# schematic.net
KiCad netlist of a schematic drawn in EAGLE
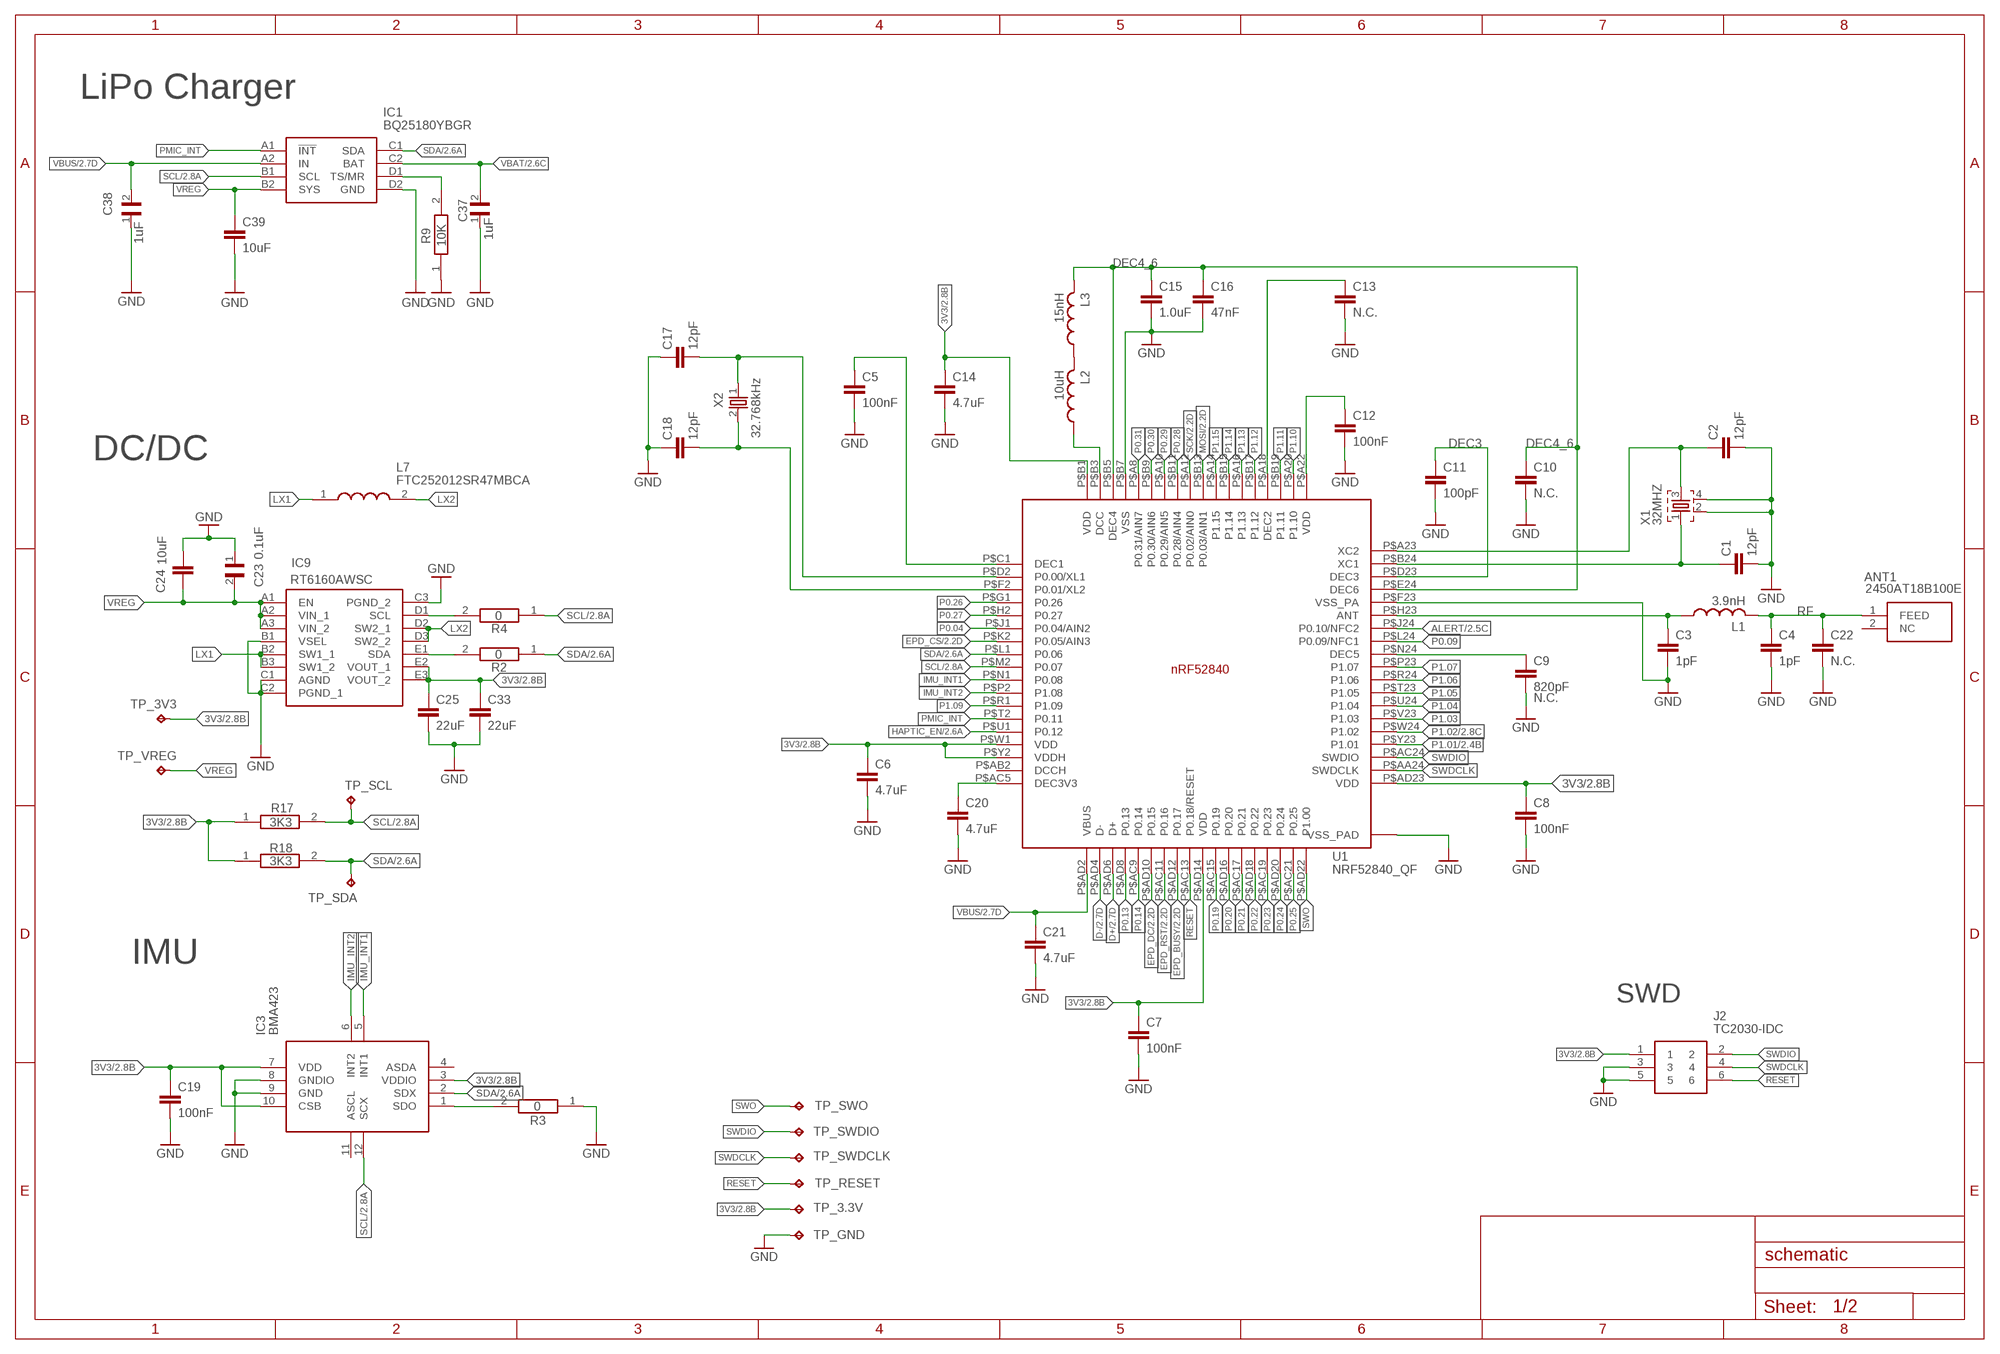
[diagram p0: schematic, sheet 1]
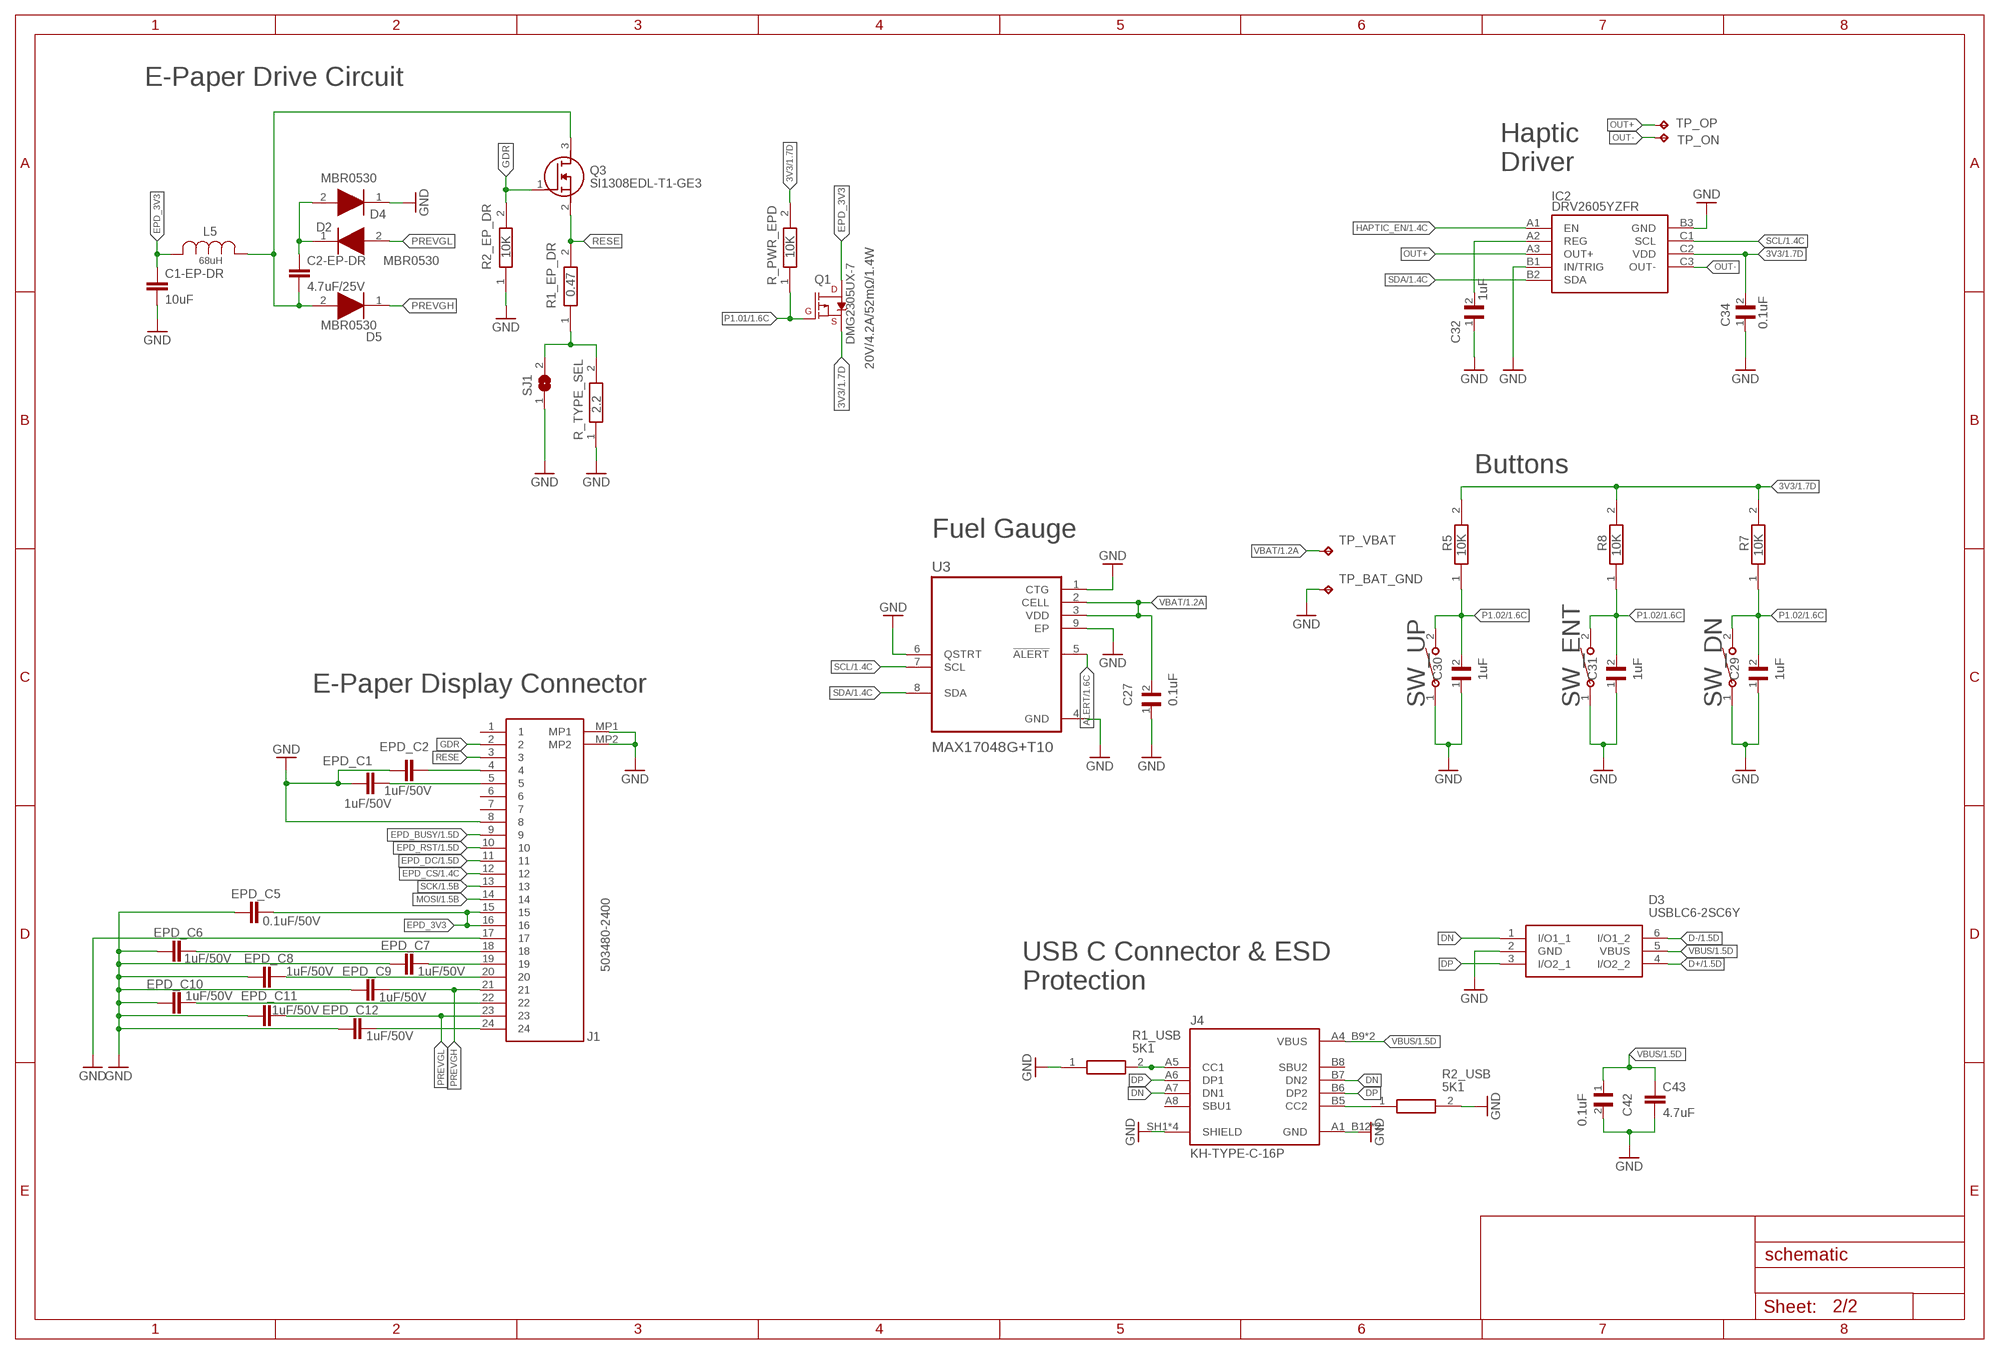
[diagram p1: schematic, sheet 2]

(export (version "E")
  (design (tool "Eeschema 10.0.6"))
  (components
    (comp (ref "ANT1")
      (value "2450AT18B100E")
      (footprint "eagle-import:2450AT18B100E_ANTC3216X140N")
      (fields (field (name "MOUSER_PART_NUMBER") "609-2450AT18B100E"))
      (libsource (lib "eagle-import") (part "2450AT18B100E_2450AT18B100E"))
    )
    (comp (ref "C1")
      (value "12pF")
      (footprint "eagle-import:NORDIC_NRF_3_RESC0201_L")
      (libsource (lib "eagle-import") (part "NORDIC_NRF_3_CAPACITOR_0201_L"))
    )
    (comp (ref "C2")
      (value "12pF")
      (footprint "eagle-import:NORDIC_NRF_3_RESC0201_L")
      (libsource (lib "eagle-import") (part "NORDIC_NRF_3_CAPACITOR_0201_L"))
    )
    (comp (ref "C3")
      (value "1pF")
      (footprint "eagle-import:NORDIC_NRF_3_RESC0201_L")
      (libsource (lib "eagle-import") (part "NORDIC_NRF_3_CAPACITOR_0201_L"))
    )
    (comp (ref "C4")
      (value "1pF")
      (footprint "eagle-import:NORDIC_NRF_3_RESC0201_L")
      (libsource (lib "eagle-import") (part "NORDIC_NRF_3_CAPACITOR_0201_L"))
    )
    (comp (ref "C5")
      (value "100nF")
      (footprint "eagle-import:NORDIC_NRF_3_RESC0201_L")
      (libsource (lib "eagle-import") (part "NORDIC_NRF_3_CAPACITOR_0201_L"))
    )
    (comp (ref "C6")
      (value "4.7uF")
      (footprint "eagle-import:NORDIC_NRF_3_RESC0402_L")
      (libsource (lib "eagle-import") (part "NORDIC_NRF_3_CAPACITOR_0402_L"))
    )
    (comp (ref "C7")
      (value "100nF")
      (footprint "eagle-import:NORDIC_NRF_3_RESC0201_L")
      (libsource (lib "eagle-import") (part "NORDIC_NRF_3_CAPACITOR_0201_L"))
    )
    (comp (ref "C8")
      (value "100nF")
      (footprint "eagle-import:NORDIC_NRF_3_RESC0201_L")
      (libsource (lib "eagle-import") (part "NORDIC_NRF_3_CAPACITOR_0201_L"))
    )
    (comp (ref "C9")
      (value "820pF")
      (footprint "eagle-import:NORDIC_NRF_3_RESC0201_L")
      (libsource (lib "eagle-import") (part "NORDIC_NRF_3_CAPACITOR_0201_L"))
    )
    (comp (ref "C10")
      (value "N.C.")
      (footprint "eagle-import:NORDIC_NRF_3_RESC0201_L")
      (libsource (lib "eagle-import") (part "NORDIC_NRF_3_CAPACITOR_0201_L"))
    )
    (comp (ref "C11")
      (value "100pF")
      (footprint "eagle-import:NORDIC_NRF_3_RESC0201_L")
      (libsource (lib "eagle-import") (part "NORDIC_NRF_3_CAPACITOR_0201_L"))
    )
    (comp (ref "C12")
      (value "100nF")
      (footprint "eagle-import:NORDIC_NRF_3_RESC0201_L")
      (libsource (lib "eagle-import") (part "NORDIC_NRF_3_CAPACITOR_0201_L"))
    )
    (comp (ref "C13")
      (value "N.C.")
      (footprint "eagle-import:NORDIC_NRF_3_RESC0201_L")
      (libsource (lib "eagle-import") (part "NORDIC_NRF_3_CAPACITOR_0201_L"))
    )
    (comp (ref "C14")
      (value "4.7uF")
      (footprint "eagle-import:NORDIC_NRF_3_RESC0201_L")
      (libsource (lib "eagle-import") (part "NORDIC_NRF_3_CAPACITOR_0201_L"))
    )
    (comp (ref "C15")
      (value "1.0uF")
      (footprint "eagle-import:NORDIC_NRF_3_RESC0201_L")
      (libsource (lib "eagle-import") (part "NORDIC_NRF_3_CAPACITOR_0201_L"))
    )
    (comp (ref "C16")
      (value "47nF")
      (footprint "eagle-import:NORDIC_NRF_3_RESC0201_L")
      (libsource (lib "eagle-import") (part "NORDIC_NRF_3_CAPACITOR_0201_L"))
    )
    (comp (ref "C17")
      (value "12pF")
      (footprint "eagle-import:PERFECT_0402_0402")
      (libsource (lib "eagle-import") (part "PERFECT_0402_CAP_0402"))
    )
    (comp (ref "C18")
      (value "12pF")
      (footprint "eagle-import:PERFECT_0402_0402")
      (libsource (lib "eagle-import") (part "PERFECT_0402_CAP_0402"))
    )
    (comp (ref "C19")
      (value "100nF")
      (footprint "eagle-import:PERFECT_0402_0402")
      (libsource (lib "eagle-import") (part "PERFECT_0402_CAP_0402"))
    )
    (comp (ref "C20")
      (value "4.7uF")
      (footprint "eagle-import:NORDIC_NRF_3_RESC0402_L")
      (libsource (lib "eagle-import") (part "NORDIC_NRF_3_CAPACITOR_0402_L"))
    )
    (comp (ref "C21")
      (value "4.7uF")
      (footprint "eagle-import:NORDIC_NRF_3_RESC0402_L")
      (libsource (lib "eagle-import") (part "NORDIC_NRF_3_CAPACITOR_0402_L"))
    )
    (comp (ref "C22")
      (value "N.C.")
      (footprint "eagle-import:NORDIC_NRF_3_RESC0201_L")
      (libsource (lib "eagle-import") (part "NORDIC_NRF_3_CAPACITOR_0201_L"))
    )
    (comp (ref "C23")
      (value "0.1uF")
      (footprint "eagle-import:GRM011R60J152KE01L_2_CAPC0201X13N")
      (fields (field (name "MF") "Murata") (field (name "MP") "GRM011R60J152KE01L"))
      (libsource (lib "eagle-import") (part "GRM011R60J152KE01L_2_GRM011R60J152KE01L"))
    )
    (comp (ref "C24")
      (value "10uF")
      (footprint "eagle-import:PERFECT_0402_0402")
      (libsource (lib "eagle-import") (part "PERFECT_0402_CAP_0402"))
    )
    (comp (ref "C25")
      (value "22uF")
      (footprint "eagle-import:PERFECT_0402_0402")
      (libsource (lib "eagle-import") (part "PERFECT_0402_CAP_0402"))
    )
    (comp (ref "C33")
      (value "22uF")
      (footprint "eagle-import:PERFECT_0402_0402")
      (libsource (lib "eagle-import") (part "PERFECT_0402_CAP_0402"))
    )
    (comp (ref "C37")
      (value "1uF")
      (footprint "eagle-import:GRM011R60J152KE01L_2_CAPC0201X13N")
      (fields (field (name "MF") "Murata") (field (name "MP") "GRM011R60J152KE01L"))
      (libsource (lib "eagle-import") (part "GRM011R60J152KE01L_2_GRM011R60J152KE01L"))
    )
    (comp (ref "C38")
      (value "1uF")
      (footprint "eagle-import:GRM011R60J152KE01L_2_CAPC0201X13N")
      (fields (field (name "MF") "Murata") (field (name "MP") "GRM011R60J152KE01L"))
      (libsource (lib "eagle-import") (part "GRM011R60J152KE01L_2_GRM011R60J152KE01L"))
    )
    (comp (ref "C39")
      (value "10uF")
      (footprint "eagle-import:PERFECT_0402_0402")
      (libsource (lib "eagle-import") (part "PERFECT_0402_CAP_0402"))
    )
    (comp (ref "IC1")
      (value "BQ25180YBGR")
      (footprint "eagle-import:BQ25180YBGR_BGA8C40P2X4_100X155X50")
      (fields (field (name "MOUSER_PART_NUMBER") "595-BQ25180YBGR"))
      (libsource (lib "eagle-import") (part "BQ25180YBGR_BQ25180YBGR"))
    )
    (comp (ref "IC3")
      (value "BMA423")
      (footprint "eagle-import:BMA423_BMA423")
      (fields (field (name "MOUSER_PART_NUMBER") "262-BMA423"))
      (libsource (lib "eagle-import") (part "BMA423_BMA423"))
    )
    (comp (ref "IC9")
      (value "RT6160AWSC")
      (footprint "eagle-import:RT6160AWSC_BGA15C40P3X5_140X230X60")
      (fields (field (name "MOUSER_PART_NUMBER") "835-RT6160AWSC"))
      (libsource (lib "eagle-import") (part "RT6160AWSC_RT6160AWSC"))
    )
    (comp (ref "J2")
      (value "TC2030-IDC")
      (footprint "eagle-import:TC2030-IDC_TC2030IDC")
      (libsource (lib "eagle-import") (part "TC2030-IDC_TC2030-IDC"))
    )
    (comp (ref "L1")
      (value "3.9nH")
      (footprint "eagle-import:NORDIC_NRF_2_RESC0201_L")
      (libsource (lib "eagle-import") (part "NORDIC_NRF_2_INDUCTOR_0201_L"))
    )
    (comp (ref "L2")
      (value "10uH")
      (footprint "eagle-import:NORDIC_NRF_2_RESC0402_L")
      (libsource (lib "eagle-import") (part "NORDIC_NRF_2_INDUCTOR_0402_L"))
    )
    (comp (ref "L3")
      (value "15nH")
      (footprint "eagle-import:NORDIC_NRF_2_RESC0402_L")
      (libsource (lib "eagle-import") (part "NORDIC_NRF_2_INDUCTOR_0402_L"))
    )
    (comp (ref "L7")
      (value "FTC252012SR47MBCA")
      (footprint "eagle-import:MLP2016SR47MT0S1_INDC2016X100N")
      (libsource (lib "eagle-import") (part "MLP2016SR47MT0S1_FTC252012SR47MBCA"))
    )
    (comp (ref "R2")
      (value "0")
      (footprint "eagle-import:ERA-1AEB3401C_0201")
      (libsource (lib "eagle-import") (part "ERA-1AEB3401C_CPF0201D7K68C1"))
    )
    (comp (ref "R3")
      (value "0")
      (footprint "eagle-import:CPF0201D7K68C1_0201")
      (libsource (lib "eagle-import") (part "CPF0201D7K68C1_CPF0201D7K68C1"))
    )
    (comp (ref "R4")
      (value "0")
      (footprint "eagle-import:ERA-1AEB3401C_0201")
      (libsource (lib "eagle-import") (part "ERA-1AEB3401C_CPF0201D7K68C1"))
    )
    (comp (ref "R9")
      (value "10K")
      (footprint "eagle-import:CPF0201D7K68C1_0201")
      (libsource (lib "eagle-import") (part "CPF0201D7K68C1_CPF0201D7K68C1"))
    )
    (comp (ref "R17")
      (value "3K3")
      (footprint "eagle-import:CPF0201D7K68C1_0201")
      (libsource (lib "eagle-import") (part "CPF0201D7K68C1_CPF0201D7K68C1"))
    )
    (comp (ref "R18")
      (value "3K3")
      (footprint "eagle-import:CPF0201D7K68C1_0201")
      (libsource (lib "eagle-import") (part "CPF0201D7K68C1_CPF0201D7K68C1"))
    )
    (comp (ref "TP_3.3V")
      (value "HECTOR_WATCH_1_TPTP20R")
      (footprint "eagle-import:HECTOR_WATCH_1_TP20R")
      (libsource (lib "eagle-import") (part "HECTOR_WATCH_1_TPTP20R"))
    )
    (comp (ref "TP_3V3")
      (value "HECTOR_WATCH_1_TPTP20R")
      (footprint "eagle-import:HECTOR_WATCH_1_TP20R")
      (libsource (lib "eagle-import") (part "HECTOR_WATCH_1_TPTP20R"))
    )
    (comp (ref "TP_GND")
      (value "HECTOR_WATCH_1_TPTP20R")
      (footprint "eagle-import:HECTOR_WATCH_1_TP20R")
      (libsource (lib "eagle-import") (part "HECTOR_WATCH_1_TPTP20R"))
    )
    (comp (ref "TP_RESET")
      (value "HECTOR_WATCH_1_TPTP20R")
      (footprint "eagle-import:HECTOR_WATCH_1_TP20R")
      (libsource (lib "eagle-import") (part "HECTOR_WATCH_1_TPTP20R"))
    )
    (comp (ref "TP_SCL")
      (value "HECTOR_WATCH_1_TPTP20R")
      (footprint "eagle-import:HECTOR_WATCH_1_TP20R")
      (libsource (lib "eagle-import") (part "HECTOR_WATCH_1_TPTP20R"))
    )
    (comp (ref "TP_SDA")
      (value "HECTOR_WATCH_1_TPTP20R")
      (footprint "eagle-import:HECTOR_WATCH_1_TP20R")
      (libsource (lib "eagle-import") (part "HECTOR_WATCH_1_TPTP20R"))
    )
    (comp (ref "TP_SWDCLK")
      (value "HECTOR_WATCH_1_TPTP20R")
      (footprint "eagle-import:HECTOR_WATCH_1_TP20R")
      (libsource (lib "eagle-import") (part "HECTOR_WATCH_1_TPTP20R"))
    )
    (comp (ref "TP_SWDIO")
      (value "HECTOR_WATCH_1_TPTP20R")
      (footprint "eagle-import:HECTOR_WATCH_1_TP20R")
      (libsource (lib "eagle-import") (part "HECTOR_WATCH_1_TPTP20R"))
    )
    (comp (ref "TP_SWO")
      (value "HECTOR_WATCH_1_TPTP20R")
      (footprint "eagle-import:HECTOR_WATCH_1_TP20R")
      (libsource (lib "eagle-import") (part "HECTOR_WATCH_1_TPTP20R"))
    )
    (comp (ref "TP_VREG")
      (value "HECTOR_WATCH_1_TPTP20R")
      (footprint "eagle-import:HECTOR_WATCH_1_TP20R")
      (libsource (lib "eagle-import") (part "HECTOR_WATCH_1_TPTP20R"))
    )
    (comp (ref "U1")
      (value "NRF52840_QF")
      (footprint "eagle-import:NORDIC_NRF_4_AQFN50P700X700X85_HS-74N")
      (libsource (lib "eagle-import") (part "NORDIC_NRF_4_NRF52840_QF"))
    )
    (comp (ref "X1")
      (value "32MHZ")
      (footprint "eagle-import:NORDIC_NRF_BT-XTAL_2016_N")
      (libsource (lib "eagle-import") (part "NORDIC_NRF_XTAL_32MHZ"))
    )
    (comp (ref "X2")
      (value "32.768kHz")
      (footprint "eagle-import:NORDIC_NRF_1_XTAL_3215_N")
      (libsource (lib "eagle-import") (part "NORDIC_NRF_1_XTAL_32KHZ"))
    )
    (comp (ref "C1-EP-DR")
      (value "10uF")
      (footprint "eagle-import:NORDIC_NRF_3_RESC0402_L")
      (libsource (lib "eagle-import") (part "NORDIC_NRF_3_CAPACITOR_0402_L"))
    )
    (comp (ref "C2-EP-DR")
      (value "4.7uF/25V")
      (footprint "eagle-import:NORDIC_NRF_3_RESC0402_L")
      (libsource (lib "eagle-import") (part "NORDIC_NRF_3_CAPACITOR_0402_L"))
    )
    (comp (ref "C27")
      (value "0.1uF")
      (footprint "eagle-import:GRM011R60J152KE01L_2_CAPC0201X13N")
      (fields (field (name "MF") "Murata") (field (name "MP") "GRM011R60J152KE01L"))
      (libsource (lib "eagle-import") (part "GRM011R60J152KE01L_2_GRM011R60J152KE01L"))
    )
    (comp (ref "C29")
      (value "1uF")
      (footprint "eagle-import:GRM011R60J152KE01L_1_0201")
      (libsource (lib "eagle-import") (part "GRM011R60J152KE01L_1_GRM011R60J152KE01L"))
    )
    (comp (ref "C30")
      (value "1uF")
      (footprint "eagle-import:GRM011R60J152KE01L_1_0201")
      (libsource (lib "eagle-import") (part "GRM011R60J152KE01L_1_GRM011R60J152KE01L"))
    )
    (comp (ref "C31")
      (value "1uF")
      (footprint "eagle-import:GRM011R60J152KE01L_1_0201")
      (libsource (lib "eagle-import") (part "GRM011R60J152KE01L_1_GRM011R60J152KE01L"))
    )
    (comp (ref "C32")
      (value "1uF")
      (footprint "eagle-import:GRM011R60J152KE01L_2_CAPC0201X13N")
      (fields (field (name "MF") "Murata") (field (name "MP") "GRM011R60J152KE01L"))
      (libsource (lib "eagle-import") (part "GRM011R60J152KE01L_2_GRM011R60J152KE01L"))
    )
    (comp (ref "C34")
      (value "0.1uF")
      (footprint "eagle-import:GRM011R60J152KE01L_2_CAPC0201X13N")
      (fields (field (name "MF") "Murata") (field (name "MP") "GRM011R60J152KE01L"))
      (libsource (lib "eagle-import") (part "GRM011R60J152KE01L_2_GRM011R60J152KE01L"))
    )
    (comp (ref "C42")
      (value "0.1uF")
      (footprint "eagle-import:GRM011R60J152KE01L_1_0201")
      (libsource (lib "eagle-import") (part "GRM011R60J152KE01L_1_GRM011R60J152KE01L"))
    )
    (comp (ref "C43")
      (value "4.7uF")
      (footprint "eagle-import:PERFECT_0402_0402")
      (libsource (lib "eagle-import") (part "PERFECT_0402_CAP_0402"))
    )
    (comp (ref "D2")
      (value "MBR0530")
      (footprint "eagle-import:ESP32_C6_LIBRARY_5_SOD3716X135N")
      (fields (field (name "MF") "ON Semiconductor"))
      (libsource (lib "eagle-import") (part "ESP32_C6_LIBRARY_5_MBR0530"))
    )
    (comp (ref "D3")
      (value "USBLC6-2SC6Y")
      (footprint "eagle-import:ESP32_C6_LIBRARY_3_SOT95P280X145-6N")
      (fields (field (name "MF") "STMicroelectronics"))
      (libsource (lib "eagle-import") (part "ESP32_C6_LIBRARY_3_USBLC6-2SC6Y"))
    )
    (comp (ref "D4")
      (value "MBR0530")
      (footprint "eagle-import:ESP32_C6_LIBRARY_5_SOD3716X135N")
      (fields (field (name "MF") "ON Semiconductor"))
      (libsource (lib "eagle-import") (part "ESP32_C6_LIBRARY_5_MBR0530"))
    )
    (comp (ref "D5")
      (value "MBR0530")
      (footprint "eagle-import:ESP32_C6_LIBRARY_5_SOD3716X135N")
      (fields (field (name "MF") "ON Semiconductor"))
      (libsource (lib "eagle-import") (part "ESP32_C6_LIBRARY_5_MBR0530"))
    )
    (comp (ref "EPD_C1")
      (value "1uF/50V")
      (footprint "eagle-import:NORDIC_NRF_3_RESC0402_L")
      (libsource (lib "eagle-import") (part "NORDIC_NRF_3_CAPACITOR_0402_L"))
    )
    (comp (ref "EPD_C2")
      (value "1uF/50V")
      (footprint "eagle-import:NORDIC_NRF_3_RESC0402_L")
      (libsource (lib "eagle-import") (part "NORDIC_NRF_3_CAPACITOR_0402_L"))
    )
    (comp (ref "EPD_C5")
      (value "0.1uF/50V")
      (footprint "eagle-import:NORDIC_NRF_3_RESC0402_L")
      (libsource (lib "eagle-import") (part "NORDIC_NRF_3_CAPACITOR_0402_L"))
    )
    (comp (ref "EPD_C6")
      (value "1uF/50V")
      (footprint "eagle-import:NORDIC_NRF_3_RESC0402_L")
      (libsource (lib "eagle-import") (part "NORDIC_NRF_3_CAPACITOR_0402_L"))
    )
    (comp (ref "EPD_C7")
      (value "1uF/50V")
      (footprint "eagle-import:NORDIC_NRF_3_RESC0402_L")
      (libsource (lib "eagle-import") (part "NORDIC_NRF_3_CAPACITOR_0402_L"))
    )
    (comp (ref "EPD_C8")
      (value "1uF/50V")
      (footprint "eagle-import:NORDIC_NRF_3_RESC0402_L")
      (libsource (lib "eagle-import") (part "NORDIC_NRF_3_CAPACITOR_0402_L"))
    )
    (comp (ref "EPD_C9")
      (value "1uF/50V")
      (footprint "eagle-import:NORDIC_NRF_3_RESC0402_L")
      (libsource (lib "eagle-import") (part "NORDIC_NRF_3_CAPACITOR_0402_L"))
    )
    (comp (ref "EPD_C10")
      (value "1uF/50V")
      (footprint "eagle-import:NORDIC_NRF_3_RESC0402_L")
      (libsource (lib "eagle-import") (part "NORDIC_NRF_3_CAPACITOR_0402_L"))
    )
    (comp (ref "EPD_C11")
      (value "1uF/50V")
      (footprint "eagle-import:NORDIC_NRF_3_RESC0402_L")
      (libsource (lib "eagle-import") (part "NORDIC_NRF_3_CAPACITOR_0402_L"))
    )
    (comp (ref "EPD_C12")
      (value "1uF/50V")
      (footprint "eagle-import:NORDIC_NRF_3_RESC0402_L")
      (libsource (lib "eagle-import") (part "NORDIC_NRF_3_CAPACITOR_0402_L"))
    )
    (comp (ref "IC2")
      (value "DRV2605YZFR")
      (footprint "eagle-import:DRV2605YZFR_BGA9C50P3X3_144X144X62")
      (libsource (lib "eagle-import") (part "DRV2605YZFR_DRV2605YZFR"))
    )
    (comp (ref "J1")
      (value "503480-2400")
      (footprint "eagle-import:503480-2400_5034802400")
      (fields (field (name "MOUSER_PART_NUMBER") "538-503480-2400"))
      (libsource (lib "eagle-import") (part "503480-2400_503480-2400"))
    )
    (comp (ref "J4")
      (value "KH-TYPE-C-16P")
      (footprint "eagle-import:KH-TYPE-C-16P_KINGHELM_KH-TYPE-C-16P")
      (fields (field (name "MF") "kinghelm"))
      (libsource (lib "eagle-import") (part "KH-TYPE-C-16P_KH-TYPE-C-16P"))
    )
    (comp (ref "L5")
      (value "68uH")
      (footprint "eagle-import:ESP32_C6_LIBRARY_2_IND_4828-WE-TPC_WRE")
      (fields
        (field (name "MANUFACTURER_PART_NUMBER") "744043680")
        (field (name "COPYRIGHT") "Copyright (C) 2024 Ultra Librarian. All rights reserved.")
      )
      (libsource (lib "eagle-import") (part "ESP32_C6_LIBRARY_2_744043680IND_4828-WE-TPC_WRE"))
    )
    (comp (ref "Q1")
      (value "20V/4.2A/52mΩ/1.4W")
      (footprint "eagle-import:ESP32_C6_LIBRARY_4_ESP32_C6_LIBRARY_4_ESP32_C6_LIBRARY_4_ESP32_C6_LIBRARY_4_ESP32_WROVER_SPARKFUN-DISCRETESEMI_SOT23-3")
      (libsource (lib "eagle-import") (part "ESP32_C6_LIBRARY_4_ESP32_WROVER_SPARKFUN-DISCRETESEMI_MOSFET_PCH-DMG2305UX-7"))
    )
    (comp (ref "Q3")
      (value "SI1308EDL-T1-GE3")
      (footprint "eagle-import:ESP32_C6_LIBRARY_6_SOT65P210X110-3N")
      (fields (field (name "MF") "Vishay Siliconix"))
      (libsource (lib "eagle-import") (part "ESP32_C6_LIBRARY_6_SI1308EDL-T1-GE3"))
    )
    (comp (ref "R1_EP_DR")
      (value "0.47")
      (footprint "eagle-import:CPF0201D7K68C1_0201")
      (libsource (lib "eagle-import") (part "CPF0201D7K68C1_CPF0201D7K68C1"))
    )
    (comp (ref "R1_USB")
      (value "5K1")
      (footprint "eagle-import:CPF0201D7K68C1_0201")
      (libsource (lib "eagle-import") (part "CPF0201D7K68C1_CPF0201D7K68C1"))
    )
    (comp (ref "R2_EP_DR")
      (value "10K")
      (footprint "eagle-import:CPF0201D7K68C1_0201")
      (libsource (lib "eagle-import") (part "CPF0201D7K68C1_CPF0201D7K68C1"))
    )
    (comp (ref "R2_USB")
      (value "5K1")
      (footprint "eagle-import:CPF0201D7K68C1_0201")
      (libsource (lib "eagle-import") (part "CPF0201D7K68C1_CPF0201D7K68C1"))
    )
    (comp (ref "R5")
      (value "10K")
      (footprint "eagle-import:CPF0201D7K68C1_0201")
      (libsource (lib "eagle-import") (part "CPF0201D7K68C1_CPF0201D7K68C1"))
    )
    (comp (ref "R7")
      (value "10K")
      (footprint "eagle-import:CPF0201D7K68C1_0201")
      (libsource (lib "eagle-import") (part "CPF0201D7K68C1_CPF0201D7K68C1"))
    )
    (comp (ref "R8")
      (value "10K")
      (footprint "eagle-import:CPF0201D7K68C1_0201")
      (libsource (lib "eagle-import") (part "CPF0201D7K68C1_CPF0201D7K68C1"))
    )
    (comp (ref "R_PWR_EPD")
      (value "10K")
      (footprint "eagle-import:CPF0201D7K68C1_0201")
      (libsource (lib "eagle-import") (part "CPF0201D7K68C1_CPF0201D7K68C1"))
    )
    (comp (ref "R_TYPE_SEL")
      (value "2.2")
      (footprint "eagle-import:CPF0201D7K68C1_0201")
      (libsource (lib "eagle-import") (part "CPF0201D7K68C1_CPF0201D7K68C1"))
    )
    (comp (ref "SJ1")
      (value "ESP32_C6_LIBRARY_7_JUMPER_SJ")
      (footprint "eagle-import:ESP32_C6_LIBRARY_7_JUMPER_SJ")
      (libsource (lib "eagle-import") (part "ESP32_C6_LIBRARY_7_JUMPER_SJ"))
    )
    (comp (ref "SW_DN")
      (value "2025-10-22_07-23-44_LIBRARY_EVP-AKE31ASW_EVP-AKE31A_PAN")
      (footprint "eagle-import:2025-10-22_07-23-44_LIBRARY_SW_EVP-AKE31A_PAN")
      (fields
        (field (name "MANUFACTURER_PART_NUMBER") "EVP-AKE31A")
        (field (name "COPYRIGHT") "Copyright (C) 2025 Ultra Librarian. All rights reserved.")
      )
      (libsource (lib "eagle-import") (part "2025-10-22_07-23-44_LIBRARY_EVP-AKE31ASW_EVP-AKE31A_PAN"))
    )
    (comp (ref "SW_ENT")
      (value "2025-10-22_07-23-44_LIBRARY_EVP-AKE31ASW_EVP-AKE31A_PAN")
      (footprint "eagle-import:2025-10-22_07-23-44_LIBRARY_SW_EVP-AKE31A_PAN")
      (fields
        (field (name "MANUFACTURER_PART_NUMBER") "EVP-AKE31A")
        (field (name "COPYRIGHT") "Copyright (C) 2025 Ultra Librarian. All rights reserved.")
      )
      (libsource (lib "eagle-import") (part "2025-10-22_07-23-44_LIBRARY_EVP-AKE31ASW_EVP-AKE31A_PAN"))
    )
    (comp (ref "SW_UP")
      (value "2025-10-22_07-23-44_LIBRARY_EVP-AKE31ASW_EVP-AKE31A_PAN")
      (footprint "eagle-import:2025-10-22_07-23-44_LIBRARY_SW_EVP-AKE31A_PAN")
      (fields
        (field (name "MANUFACTURER_PART_NUMBER") "EVP-AKE31A")
        (field (name "COPYRIGHT") "Copyright (C) 2025 Ultra Librarian. All rights reserved.")
      )
      (libsource (lib "eagle-import") (part "2025-10-22_07-23-44_LIBRARY_EVP-AKE31ASW_EVP-AKE31A_PAN"))
    )
    (comp (ref "TP_BAT_GND")
      (value "HECTOR_WATCH_1_TPTP20R")
      (footprint "eagle-import:HECTOR_WATCH_1_TP20R")
      (libsource (lib "eagle-import") (part "HECTOR_WATCH_1_TPTP20R"))
    )
    (comp (ref "TP_ON")
      (value "HECTOR_WATCH_1_TPTP20R")
      (footprint "eagle-import:HECTOR_WATCH_1_TP20R")
      (libsource (lib "eagle-import") (part "HECTOR_WATCH_1_TPTP20R"))
    )
    (comp (ref "TP_OP")
      (value "HECTOR_WATCH_1_TPTP20R")
      (footprint "eagle-import:HECTOR_WATCH_1_TP20R")
      (libsource (lib "eagle-import") (part "HECTOR_WATCH_1_TPTP20R"))
    )
    (comp (ref "TP_VBAT")
      (value "HECTOR_WATCH_1_TPTP20R")
      (footprint "eagle-import:HECTOR_WATCH_1_TP20R")
      (libsource (lib "eagle-import") (part "HECTOR_WATCH_1_TPTP20R"))
    )
    (comp (ref "U3")
      (value "MAX17048G+T10")
      (footprint "eagle-import:ESP32_C6_LIBRARY_SON50P200X200X80-9N")
      (fields (field (name "MF") "Analog Devices"))
      (libsource (lib "eagle-import") (part "ESP32_C6_LIBRARY_MAX17048G+T10"))
    )
  )
  (nets
    (net (code "1") (name "3V3") (class "Default")
      (node (ref "C14") (pin "1") (pinfunction "1_1") (pintype "passive"))
      (node (ref "C19") (pin "1") (pinfunction "1_1") (pintype "passive"))
      (node (ref "C25") (pin "1") (pinfunction "1_1") (pintype "passive"))
      (node (ref "C33") (pin "1") (pinfunction "1_1") (pintype "passive"))
      (node (ref "C34") (pin "2") (pinfunction "2_2") (pintype "passive"))
      (node (ref "C6") (pin "1") (pinfunction "1_1") (pintype "passive"))
      (node (ref "C7") (pin "1") (pinfunction "1_1") (pintype "passive"))
      (node (ref "C8") (pin "1") (pinfunction "1_1") (pintype "passive"))
      (node (ref "IC2") (pin "C2") (pinfunction "VDD_C2") (pintype "bidirectional"))
      (node (ref "IC3") (pin "10") (pinfunction "CSB_10") (pintype "bidirectional"))
      (node (ref "IC3") (pin "3") (pinfunction "VDDIO_3") (pintype "bidirectional"))
      (node (ref "IC3") (pin "7") (pinfunction "VDD_7") (pintype "bidirectional"))
      (node (ref "IC9") (pin "E2") (pinfunction "VOUT_1_E2") (pintype "bidirectional"))
      (node (ref "IC9") (pin "E3") (pinfunction "VOUT_2_E3") (pintype "bidirectional"))
      (node (ref "J2") (pin "1") (pinfunction "1_1") (pintype "bidirectional"))
      (node (ref "Q1") (pin "2") (pinfunction "S_2") (pintype "bidirectional"))
      (node (ref "R17") (pin "1") (pinfunction "1_1") (pintype "bidirectional"))
      (node (ref "R18") (pin "1") (pinfunction "1_1") (pintype "bidirectional"))
      (node (ref "R5") (pin "2") (pinfunction "2_2") (pintype "bidirectional"))
      (node (ref "R7") (pin "2") (pinfunction "2_2") (pintype "bidirectional"))
      (node (ref "R8") (pin "2") (pinfunction "2_2") (pintype "bidirectional"))
      (node (ref "R_PWR_EPD") (pin "2") (pinfunction "2_2") (pintype "bidirectional"))
      (node (ref "TP_3.3V") (pin "TP") (pinfunction "TP_TP") (pintype "input"))
      (node (ref "TP_3V3") (pin "TP") (pinfunction "TP_TP") (pintype "input"))
      (node (ref "U1") (pin "P$AD14") (pinfunction "VDD_P$AD14") (pintype "power_in"))
      (node (ref "U1") (pin "P$AD23") (pinfunction "VDD_P$AD23") (pintype "power_in"))
      (node (ref "U1") (pin "P$B1") (pinfunction "VDD_P$B1") (pintype "power_in"))
      (node (ref "U1") (pin "P$W1") (pinfunction "VDD_P$W1") (pintype "power_in"))
      (node (ref "U1") (pin "P$Y2") (pinfunction "VDDH_P$Y2") (pintype "power_in"))
    )
    (net (code "2") (name "ALERT") (class "Default")
      (node (ref "U1") (pin "P$J24") (pinfunction "P0.10/NFC2_P$J24") (pintype "bidirectional"))
      (node (ref "U3") (pin "5") (pinfunction "~{ALERT}_5") (pintype "output"))
    )
    (net (code "3") (name "D+") (class "Default")
      (node (ref "D3") (pin "4") (pinfunction "I/O2_2_4") (pintype "bidirectional"))
      (node (ref "U1") (pin "P$AD6") (pinfunction "D+_P$AD6") (pintype "bidirectional"))
    )
    (net (code "4") (name "D-") (class "Default")
      (node (ref "D3") (pin "6") (pinfunction "I/O1_2_6") (pintype "bidirectional"))
      (node (ref "U1") (pin "P$AD4") (pinfunction "D-_P$AD4") (pintype "bidirectional"))
    )
    (net (code "5") (name "DEC4_6") (class "Default")
      (node (ref "C10") (pin "1") (pinfunction "1_1") (pintype "passive"))
      (node (ref "C15") (pin "1") (pinfunction "1_1") (pintype "passive"))
      (node (ref "C16") (pin "1") (pinfunction "1_1") (pintype "passive"))
      (node (ref "L3") (pin "2") (pinfunction "2_2") (pintype "passive"))
      (node (ref "U1") (pin "P$B5") (pinfunction "DEC4_P$B5") (pintype "power_in"))
      (node (ref "U1") (pin "P$E24") (pinfunction "DEC6_P$E24") (pintype "bidirectional"))
    )
    (net (code "6") (name "DN") (class "Default")
      (node (ref "D3") (pin "1") (pinfunction "I/O1_1_1") (pintype "bidirectional"))
      (node (ref "J4") (pin "A7") (pinfunction "DN1_A7") (pintype "bidirectional"))
      (node (ref "J4") (pin "B7") (pinfunction "DN2_B7") (pintype "bidirectional"))
    )
    (net (code "7") (name "DP") (class "Default")
      (node (ref "D3") (pin "3") (pinfunction "I/O2_1_3") (pintype "bidirectional"))
      (node (ref "J4") (pin "A6") (pinfunction "DP1_A6") (pintype "bidirectional"))
      (node (ref "J4") (pin "B6") (pinfunction "DP2_B6") (pintype "bidirectional"))
    )
    (net (code "8") (name "EPD_3V3") (class "Default")
      (node (ref "C1-EP-DR") (pin "1") (pinfunction "1_1") (pintype "passive"))
      (node (ref "EPD_C5") (pin "2") (pinfunction "2_2") (pintype "passive"))
      (node (ref "J1") (pin "15") (pinfunction "15_15") (pintype "bidirectional"))
      (node (ref "J1") (pin "16") (pinfunction "16_16") (pintype "bidirectional"))
      (node (ref "L5") (pin "2") (pinfunction "2_2") (pintype "passive"))
      (node (ref "Q1") (pin "3") (pinfunction "D_3") (pintype "bidirectional"))
    )
    (net (code "9") (name "EPD_BUSY") (class "Default")
      (node (ref "J1") (pin "9") (pinfunction "9_9") (pintype "bidirectional"))
      (node (ref "U1") (pin "P$AD12") (pinfunction "P0.17_P$AD12") (pintype "bidirectional"))
    )
    (net (code "10") (name "EPD_CS") (class "Default")
      (node (ref "J1") (pin "12") (pinfunction "12_12") (pintype "bidirectional"))
      (node (ref "U1") (pin "P$K2") (pinfunction "P0.05/AIN3_P$K2") (pintype "bidirectional"))
    )
    (net (code "11") (name "EPD_DC") (class "Default")
      (node (ref "J1") (pin "11") (pinfunction "11_11") (pintype "bidirectional"))
      (node (ref "U1") (pin "P$AD10") (pinfunction "P0.15_P$AD10") (pintype "bidirectional"))
    )
    (net (code "12") (name "EPD_RST") (class "Default")
      (node (ref "J1") (pin "10") (pinfunction "10_10") (pintype "bidirectional"))
      (node (ref "U1") (pin "P$AC11") (pinfunction "P0.16_P$AC11") (pintype "bidirectional"))
    )
    (net (code "13") (name "GDR") (class "Default")
      (node (ref "J1") (pin "2") (pinfunction "2_2") (pintype "bidirectional"))
      (node (ref "Q3") (pin "1") (pinfunction "G_1") (pintype "bidirectional"))
      (node (ref "R2_EP_DR") (pin "2") (pinfunction "2_2") (pintype "bidirectional"))
    )
    (net (code "14") (name "GND") (class "Default")
      (node (ref "C1") (pin "2") (pinfunction "2_2") (pintype "passive"))
      (node (ref "C1-EP-DR") (pin "2") (pinfunction "2_2") (pintype "passive"))
      (node (ref "C10") (pin "2") (pinfunction "2_2") (pintype "passive"))
      (node (ref "C11") (pin "2") (pinfunction "2_2") (pintype "passive"))
      (node (ref "C12") (pin "2") (pinfunction "2_2") (pintype "passive"))
      (node (ref "C13") (pin "2") (pinfunction "2_2") (pintype "passive"))
      (node (ref "C14") (pin "2") (pinfunction "2_2") (pintype "passive"))
      (node (ref "C15") (pin "2") (pinfunction "2_2") (pintype "passive"))
      (node (ref "C16") (pin "2") (pinfunction "2_2") (pintype "passive"))
      (node (ref "C17") (pin "1") (pinfunction "1_1") (pintype "passive"))
      (node (ref "C18") (pin "1") (pinfunction "1_1") (pintype "passive"))
      (node (ref "C19") (pin "2") (pinfunction "2_2") (pintype "passive"))
      (node (ref "C2") (pin "2") (pinfunction "2_2") (pintype "passive"))
      (node (ref "C20") (pin "2") (pinfunction "2_2") (pintype "passive"))
      (node (ref "C21") (pin "2") (pinfunction "2_2") (pintype "passive"))
      (node (ref "C22") (pin "2") (pinfunction "2_2") (pintype "passive"))
      (node (ref "C23") (pin "1") (pinfunction "1_1") (pintype "passive"))
      (node (ref "C24") (pin "1") (pinfunction "1_1") (pintype "passive"))
      (node (ref "C25") (pin "2") (pinfunction "2_2") (pintype "passive"))
      (node (ref "C27") (pin "1") (pinfunction "1_1") (pintype "passive"))
      (node (ref "C29") (pin "1") (pinfunction "1_1") (pintype "passive"))
      (node (ref "C3") (pin "2") (pinfunction "2_2") (pintype "passive"))
      (node (ref "C30") (pin "1") (pinfunction "1_1") (pintype "passive"))
      (node (ref "C31") (pin "1") (pinfunction "1_1") (pintype "passive"))
      (node (ref "C32") (pin "1") (pinfunction "1_1") (pintype "passive"))
      (node (ref "C33") (pin "2") (pinfunction "2_2") (pintype "passive"))
      (node (ref "C34") (pin "1") (pinfunction "1_1") (pintype "passive"))
      (node (ref "C37") (pin "1") (pinfunction "1_1") (pintype "passive"))
      (node (ref "C38") (pin "1") (pinfunction "1_1") (pintype "passive"))
      (node (ref "C39") (pin "2") (pinfunction "2_2") (pintype "passive"))
      (node (ref "C4") (pin "2") (pinfunction "2_2") (pintype "passive"))
      (node (ref "C42") (pin "2") (pinfunction "2_2") (pintype "passive"))
      (node (ref "C43") (pin "2") (pinfunction "2_2") (pintype "passive"))
      (node (ref "C5") (pin "2") (pinfunction "2_2") (pintype "passive"))
      (node (ref "C6") (pin "2") (pinfunction "2_2") (pintype "passive"))
      (node (ref "C7") (pin "2") (pinfunction "2_2") (pintype "passive"))
      (node (ref "C8") (pin "2") (pinfunction "2_2") (pintype "passive"))
      (node (ref "C9") (pin "2") (pinfunction "2_2") (pintype "passive"))
      (node (ref "D3") (pin "2") (pinfunction "GND_2") (pintype "bidirectional"))
      (node (ref "D4") (pin "1") (pinfunction "K_1") (pintype "bidirectional"))
      (node (ref "EPD_C1") (pin "1") (pinfunction "1_1") (pintype "passive"))
      (node (ref "EPD_C10") (pin "1") (pinfunction "1_1") (pintype "passive"))
      (node (ref "EPD_C11") (pin "1") (pinfunction "1_1") (pintype "passive"))
      (node (ref "EPD_C12") (pin "1") (pinfunction "1_1") (pintype "passive"))
      (node (ref "EPD_C2") (pin "1") (pinfunction "1_1") (pintype "passive"))
      (node (ref "EPD_C5") (pin "1") (pinfunction "1_1") (pintype "passive"))
      (node (ref "EPD_C6") (pin "1") (pinfunction "1_1") (pintype "passive"))
      (node (ref "EPD_C7") (pin "1") (pinfunction "1_1") (pintype "passive"))
      (node (ref "EPD_C8") (pin "1") (pinfunction "1_1") (pintype "passive"))
      (node (ref "EPD_C9") (pin "1") (pinfunction "1_1") (pintype "passive"))
      (node (ref "IC1") (pin "D2") (pinfunction "GND_D2") (pintype "bidirectional"))
      (node (ref "IC2") (pin "B1") (pinfunction "IN/TRIG_B1") (pintype "bidirectional"))
      (node (ref "IC2") (pin "B3") (pinfunction "GND_B3") (pintype "bidirectional"))
      (node (ref "IC3") (pin "8") (pinfunction "GNDIO_8") (pintype "bidirectional"))
      (node (ref "IC3") (pin "9") (pinfunction "GND_9") (pintype "bidirectional"))
      (node (ref "IC9") (pin "B1") (pinfunction "VSEL_B1") (pintype "bidirectional"))
      (node (ref "IC9") (pin "C1") (pinfunction "AGND_C1") (pintype "bidirectional"))
      (node (ref "IC9") (pin "C2") (pinfunction "PGND_1_C2") (pintype "bidirectional"))
      (node (ref "IC9") (pin "C3") (pinfunction "PGND_2_C3") (pintype "bidirectional"))
      (node (ref "J1") (pin "17") (pinfunction "17_17") (pintype "bidirectional"))
      (node (ref "J1") (pin "8") (pinfunction "8_8") (pintype "bidirectional"))
      (node (ref "J1") (pin "MP1") (pinfunction "MP1_MP1") (pintype "bidirectional"))
      (node (ref "J1") (pin "MP2") (pinfunction "MP2_MP2") (pintype "bidirectional"))
      (node (ref "J2") (pin "3") (pinfunction "3_3") (pintype "bidirectional"))
      (node (ref "J2") (pin "5") (pinfunction "5_5") (pintype "bidirectional"))
      (node (ref "J4") (pin "A12_B1") (pinfunction "GND_A12_B1") (pintype "power_in"))
      (node (ref "J4") (pin "A1_B12") (pinfunction "GND_A1_B12") (pintype "power_in"))
      (node (ref "J4") (pin "SH1") (pinfunction "SHIELD_SH1") (pintype "passive"))
      (node (ref "J4") (pin "SH2") (pinfunction "SHIELD_SH2") (pintype "passive"))
      (node (ref "J4") (pin "SH3") (pinfunction "SHIELD_SH3") (pintype "passive"))
      (node (ref "J4") (pin "SH4") (pinfunction "SHIELD_SH4") (pintype "passive"))
      (node (ref "R1_USB") (pin "1") (pinfunction "1_1") (pintype "bidirectional"))
      (node (ref "R2_EP_DR") (pin "1") (pinfunction "1_1") (pintype "bidirectional"))
      (node (ref "R2_USB") (pin "2") (pinfunction "2_2") (pintype "bidirectional"))
      (node (ref "R3") (pin "1") (pinfunction "1_1") (pintype "bidirectional"))
      (node (ref "R9") (pin "1") (pinfunction "1_1") (pintype "bidirectional"))
      (node (ref "R_TYPE_SEL") (pin "1") (pinfunction "1_1") (pintype "bidirectional"))
      (node (ref "SJ1") (pin "1") (pinfunction "1_1") (pintype "passive"))
      (node (ref "SW_DN") (pin "1") (pinfunction "1_1") (pintype "passive"))
      (node (ref "SW_ENT") (pin "1") (pinfunction "1_1") (pintype "passive"))
      (node (ref "SW_UP") (pin "1") (pinfunction "1_1") (pintype "passive"))
      (node (ref "TP_BAT_GND") (pin "TP") (pinfunction "TP_TP") (pintype "input"))
      (node (ref "TP_GND") (pin "TP") (pinfunction "TP_TP") (pintype "input"))
      (node (ref "U1") (pin "P$74") (pinfunction "VSS_PAD_P$74") (pintype "bidirectional"))
      (node (ref "U1") (pin "P$75") (pinfunction "VSS_PAD_P$75") (pintype "bidirectional"))
      (node (ref "U1") (pin "P$76") (pinfunction "VSS_PAD_P$76") (pintype "bidirectional"))
      (node (ref "U1") (pin "P$77") (pinfunction "VSS_PAD_P$77") (pintype "bidirectional"))
      (node (ref "U1") (pin "P$78") (pinfunction "VSS_PAD_P$78") (pintype "bidirectional"))
      (node (ref "U1") (pin "P$79") (pinfunction "VSS_PAD_P$79") (pintype "bidirectional"))
      (node (ref "U1") (pin "P$80") (pinfunction "VSS_PAD_P$80") (pintype "bidirectional"))
      (node (ref "U1") (pin "P$81") (pinfunction "VSS_PAD_P$81") (pintype "bidirectional"))
      (node (ref "U1") (pin "P$82") (pinfunction "VSS_PAD_P$82") (pintype "bidirectional"))
      (node (ref "U1") (pin "P$83") (pinfunction "VSS_PAD_P$83") (pintype "bidirectional"))
      (node (ref "U1") (pin "P$84") (pinfunction "VSS_PAD_P$84") (pintype "bidirectional"))
      (node (ref "U1") (pin "P$85") (pinfunction "VSS_PAD_P$85") (pintype "bidirectional"))
      (node (ref "U1") (pin "P$86") (pinfunction "VSS_PAD_P$86") (pintype "bidirectional"))
      (node (ref "U1") (pin "P$87") (pinfunction "VSS_PAD_P$87") (pintype "bidirectional"))
      (node (ref "U1") (pin "P$88") (pinfunction "VSS_PAD_P$88") (pintype "bidirectional"))
      (node (ref "U1") (pin "P$89") (pinfunction "VSS_PAD_P$89") (pintype "bidirectional"))
      (node (ref "U1") (pin "P$90") (pinfunction "VSS_PAD_P$90") (pintype "bidirectional"))
      (node (ref "U1") (pin "P$B7") (pinfunction "VSS_P$B7") (pintype "power_in"))
      (node (ref "U1") (pin "P$F23") (pinfunction "VSS_PA_P$F23") (pintype "bidirectional"))
      (node (ref "U3") (pin "1") (pinfunction "CTG_1") (pintype "power_in"))
      (node (ref "U3") (pin "4") (pinfunction "GND_4") (pintype "power_in"))
      (node (ref "U3") (pin "6") (pinfunction "QSTRT_6") (pintype "input"))
      (node (ref "U3") (pin "9") (pinfunction "EP_9") (pintype "power_in"))
      (node (ref "X1") (pin "2") (pinfunction "2_2") (pintype "passive"))
      (node (ref "X1") (pin "4") (pinfunction "4_4") (pintype "passive"))
    )
    (net (code "15") (name "HAPTIC_EN") (class "Default")
      (node (ref "IC2") (pin "A1") (pinfunction "EN_A1") (pintype "bidirectional"))
      (node (ref "U1") (pin "P$U1") (pinfunction "P0.12_P$U1") (pintype "bidirectional"))
    )
    (net (code "16") (name "IMU_INT1") (class "Default")
      (node (ref "IC3") (pin "5") (pinfunction "INT1_5") (pintype "bidirectional"))
      (node (ref "U1") (pin "P$N1") (pinfunction "P0.08_P$N1") (pintype "bidirectional"))
    )
    (net (code "17") (name "IMU_INT2") (class "Default")
      (node (ref "IC3") (pin "6") (pinfunction "INT2_6") (pintype "bidirectional"))
      (node (ref "U1") (pin "P$P2") (pinfunction "P1.08_P$P2") (pintype "bidirectional"))
    )
    (net (code "18") (name "LX1") (class "Default")
      (node (ref "IC9") (pin "B2") (pinfunction "SW1_1_B2") (pintype "bidirectional"))
      (node (ref "IC9") (pin "B3") (pinfunction "SW1_2_B3") (pintype "bidirectional"))
      (node (ref "L7") (pin "1") (pinfunction "1_1") (pintype "bidirectional"))
    )
    (net (code "19") (name "LX2") (class "Default")
      (node (ref "IC9") (pin "D2") (pinfunction "SW2_1_D2") (pintype "bidirectional"))
      (node (ref "IC9") (pin "D3") (pinfunction "SW2_2_D3") (pintype "bidirectional"))
      (node (ref "L7") (pin "2") (pinfunction "2_2") (pintype "bidirectional"))
    )
    (net (code "20") (name "MOSI") (class "Default")
      (node (ref "J1") (pin "14") (pinfunction "14_14") (pintype "bidirectional"))
      (node (ref "U1") (pin "P$B13") (pinfunction "P0.03/AIN1_P$B13") (pintype "bidirectional"))
    )
    (net (code "21") (name "Net-(ANT1-FEED)") (class "Default")
      (node (ref "ANT1") (pin "1") (pinfunction "FEED_1") (pintype "input"))
      (node (ref "C22") (pin "1") (pinfunction "1_1") (pintype "passive"))
      (node (ref "C4") (pin "1") (pinfunction "1_1") (pintype "passive"))
      (node (ref "L1") (pin "2") (pinfunction "2_2") (pintype "passive"))
    )
    (net (code "22") (name "Net-(C12-Pad1)") (class "Default")
      (node (ref "C12") (pin "1") (pinfunction "1_1") (pintype "passive"))
      (node (ref "U1") (pin "P$A22") (pinfunction "VDD_P$A22") (pintype "power_in"))
    )
    (net (code "23") (name "Net-(D2-K)") (class "Default")
      (node (ref "C2-EP-DR") (pin "1") (pinfunction "1_1") (pintype "passive"))
      (node (ref "D2") (pin "1") (pinfunction "K_1") (pintype "bidirectional"))
      (node (ref "D4") (pin "2") (pinfunction "A_2") (pintype "bidirectional"))
    )
    (net (code "24") (name "Net-(D5-A)") (class "Default")
      (node (ref "C2-EP-DR") (pin "2") (pinfunction "2_2") (pintype "passive"))
      (node (ref "D5") (pin "2") (pinfunction "A_2") (pintype "bidirectional"))
      (node (ref "L5") (pin "1") (pinfunction "1_1") (pintype "passive"))
      (node (ref "Q3") (pin "3") (pinfunction "D_3") (pintype "bidirectional"))
    )
    (net (code "25") (name "Net-(EPD_C1-Pad2)") (class "Default")
      (node (ref "EPD_C1") (pin "2") (pinfunction "2_2") (pintype "passive"))
      (node (ref "J1") (pin "5") (pinfunction "5_5") (pintype "bidirectional"))
    )
    (net (code "26") (name "Net-(EPD_C2-Pad2)") (class "Default")
      (node (ref "EPD_C2") (pin "2") (pinfunction "2_2") (pintype "passive"))
      (node (ref "J1") (pin "4") (pinfunction "4_4") (pintype "bidirectional"))
    )
    (net (code "27") (name "Net-(EPD_C6-Pad2)") (class "Default")
      (node (ref "EPD_C6") (pin "2") (pinfunction "2_2") (pintype "passive"))
      (node (ref "J1") (pin "18") (pinfunction "18_18") (pintype "bidirectional"))
    )
    (net (code "28") (name "Net-(EPD_C7-Pad2)") (class "Default")
      (node (ref "EPD_C7") (pin "2") (pinfunction "2_2") (pintype "passive"))
      (node (ref "J1") (pin "19") (pinfunction "19_19") (pintype "bidirectional"))
    )
    (net (code "29") (name "Net-(EPD_C8-Pad2)") (class "Default")
      (node (ref "EPD_C8") (pin "2") (pinfunction "2_2") (pintype "passive"))
      (node (ref "J1") (pin "20") (pinfunction "20_20") (pintype "bidirectional"))
    )
    (net (code "30") (name "Net-(EPD_C10-Pad2)") (class "Default")
      (node (ref "EPD_C10") (pin "2") (pinfunction "2_2") (pintype "passive"))
      (node (ref "J1") (pin "22") (pinfunction "22_22") (pintype "bidirectional"))
    )
    (net (code "31") (name "Net-(EPD_C12-Pad2)") (class "Default")
      (node (ref "EPD_C12") (pin "2") (pinfunction "2_2") (pintype "passive"))
      (node (ref "J1") (pin "24") (pinfunction "24_24") (pintype "bidirectional"))
    )
    (net (code "32") (name "Net-(IC1-TS{slash}MR)") (class "Default")
      (node (ref "IC1") (pin "D1") (pinfunction "TS/MR_D1") (pintype "bidirectional"))
      (node (ref "R9") (pin "2") (pinfunction "2_2") (pintype "bidirectional"))
    )
    (net (code "33") (name "Net-(IC2-REG)") (class "Default")
      (node (ref "C32") (pin "2") (pinfunction "2_2") (pintype "passive"))
      (node (ref "IC2") (pin "A2") (pinfunction "REG_A2") (pintype "bidirectional"))
    )
    (net (code "34") (name "Net-(IC3-SDO)") (class "Default")
      (node (ref "IC3") (pin "1") (pinfunction "SDO_1") (pintype "bidirectional"))
      (node (ref "R3") (pin "2") (pinfunction "2_2") (pintype "bidirectional"))
    )
    (net (code "35") (name "Net-(IC9-SCL)") (class "Default")
      (node (ref "IC9") (pin "D1") (pinfunction "SCL_D1") (pintype "bidirectional"))
      (node (ref "R4") (pin "2") (pinfunction "2_2") (pintype "bidirectional"))
    )
    (net (code "36") (name "Net-(IC9-SDA)") (class "Default")
      (node (ref "IC9") (pin "E1") (pinfunction "SDA_E1") (pintype "bidirectional"))
      (node (ref "R2") (pin "2") (pinfunction "2_2") (pintype "bidirectional"))
    )
    (net (code "37") (name "Net-(J4-CC1)") (class "Default")
      (node (ref "J4") (pin "A5") (pinfunction "CC1_A5") (pintype "bidirectional"))
      (node (ref "R1_USB") (pin "2") (pinfunction "2_2") (pintype "bidirectional"))
    )
    (net (code "38") (name "Net-(J4-CC2)") (class "Default")
      (node (ref "J4") (pin "B5") (pinfunction "CC2_B5") (pintype "bidirectional"))
      (node (ref "R2_USB") (pin "1") (pinfunction "1_1") (pintype "bidirectional"))
    )
    (net (code "39") (name "Net-(L2-Pad2)") (class "Default")
      (node (ref "L2") (pin "2") (pinfunction "2_2") (pintype "passive"))
      (node (ref "L3") (pin "1") (pinfunction "1_1") (pintype "passive"))
    )
    (net (code "40") (name "Net-(R1_EP_DR-Pad1)") (class "Default")
      (node (ref "R1_EP_DR") (pin "1") (pinfunction "1_1") (pintype "bidirectional"))
      (node (ref "R_TYPE_SEL") (pin "2") (pinfunction "2_2") (pintype "bidirectional"))
      (node (ref "SJ1") (pin "2") (pinfunction "2_2") (pintype "passive"))
    )
    (net (code "41") (name "Net-(U1-ANT)") (class "Default")
      (node (ref "C3") (pin "1") (pinfunction "1_1") (pintype "passive"))
      (node (ref "L1") (pin "1") (pinfunction "1_1") (pintype "passive"))
      (node (ref "U1") (pin "P$H23") (pinfunction "ANT_P$H23") (pintype "bidirectional"))
    )
    (net (code "42") (name "Net-(U1-DCC)") (class "Default")
      (node (ref "L2") (pin "1") (pinfunction "1_1") (pintype "passive"))
      (node (ref "U1") (pin "P$B3") (pinfunction "DCC_P$B3") (pintype "output"))
    )
    (net (code "43") (name "Net-(U1-DEC1)") (class "Default")
      (node (ref "C5") (pin "1") (pinfunction "1_1") (pintype "passive"))
      (node (ref "U1") (pin "P$C1") (pinfunction "DEC1_P$C1") (pintype "power_in"))
    )
    (net (code "44") (name "Net-(U1-DEC2)") (class "Default")
      (node (ref "C13") (pin "1") (pinfunction "1_1") (pintype "passive"))
      (node (ref "U1") (pin "P$A18") (pinfunction "DEC2_P$A18") (pintype "bidirectional"))
    )
    (net (code "45") (name "Net-(U1-DEC3)") (class "Default")
      (node (ref "C11") (pin "1") (pinfunction "1_1") (pintype "passive"))
      (node (ref "U1") (pin "P$D23") (pinfunction "DEC3_P$D23") (pintype "bidirectional"))
    )
    (net (code "46") (name "Net-(U1-DEC3V3)") (class "Default")
      (node (ref "C20") (pin "1") (pinfunction "1_1") (pintype "passive"))
      (node (ref "U1") (pin "P$AC5") (pinfunction "DEC3V3_P$AC5") (pintype "bidirectional"))
    )
    (net (code "47") (name "Net-(U1-DEC5)") (class "Default")
      (node (ref "C9") (pin "1") (pinfunction "1_1") (pintype "passive"))
      (node (ref "U1") (pin "P$N24") (pinfunction "DEC5_P$N24") (pintype "bidirectional"))
    )
    (net (code "48") (name "Net-(U1-P0.00{slash}XL1)") (class "Default")
      (node (ref "C17") (pin "2") (pinfunction "2_2") (pintype "passive"))
      (node (ref "U1") (pin "P$D2") (pinfunction "P0.00/XL1_P$D2") (pintype "bidirectional"))
      (node (ref "X2") (pin "1") (pinfunction "1_1") (pintype "passive"))
    )
    (net (code "49") (name "Net-(U1-P0.01{slash}XL2)") (class "Default")
      (node (ref "C18") (pin "2") (pinfunction "2_2") (pintype "passive"))
      (node (ref "U1") (pin "P$F2") (pinfunction "P0.01/XL2_P$F2") (pintype "bidirectional"))
      (node (ref "X2") (pin "2") (pinfunction "2_2") (pintype "passive"))
    )
    (net (code "50") (name "Net-(U1-XC1)") (class "Default")
      (node (ref "C1") (pin "1") (pinfunction "1_1") (pintype "passive"))
      (node (ref "U1") (pin "P$B24") (pinfunction "XC1_P$B24") (pintype "input"))
      (node (ref "X1") (pin "1") (pinfunction "1_1") (pintype "passive"))
    )
    (net (code "51") (name "Net-(U1-XC2)") (class "Default")
      (node (ref "C2") (pin "1") (pinfunction "1_1") (pintype "passive"))
      (node (ref "U1") (pin "P$A23") (pinfunction "XC2_P$A23") (pintype "output"))
      (node (ref "X1") (pin "3") (pinfunction "3_3") (pintype "passive"))
    )
    (net (code "52") (name "OUT+") (class "Default")
      (node (ref "IC2") (pin "A3") (pinfunction "OUT+_A3") (pintype "bidirectional"))
      (node (ref "TP_OP") (pin "TP") (pinfunction "TP_TP") (pintype "input"))
    )
    (net (code "53") (name "OUT-") (class "Default")
      (node (ref "IC2") (pin "C3") (pinfunction "OUT-_C3") (pintype "bidirectional"))
      (node (ref "TP_ON") (pin "TP") (pinfunction "TP_TP") (pintype "input"))
    )
    (net (code "54") (name "P0.04") (class "Default")
      (node (ref "U1") (pin "P$J1") (pinfunction "P0.04/AIN2_P$J1") (pintype "bidirectional"))
    )
    (net (code "55") (name "P0.09") (class "Default")
      (node (ref "U1") (pin "P$L24") (pinfunction "P0.09/NFC1_P$L24") (pintype "bidirectional"))
    )
    (net (code "56") (name "P0.13") (class "Default")
      (node (ref "U1") (pin "P$AD8") (pinfunction "P0.13_P$AD8") (pintype "bidirectional"))
    )
    (net (code "57") (name "P0.14") (class "Default")
      (node (ref "U1") (pin "P$AC9") (pinfunction "P0.14_P$AC9") (pintype "bidirectional"))
    )
    (net (code "58") (name "P0.19") (class "Default")
      (node (ref "U1") (pin "P$AC15") (pinfunction "P0.19_P$AC15") (pintype "bidirectional"))
    )
    (net (code "59") (name "P0.20") (class "Default")
      (node (ref "U1") (pin "P$AD16") (pinfunction "P0.20_P$AD16") (pintype "bidirectional"))
    )
    (net (code "60") (name "P0.21") (class "Default")
      (node (ref "U1") (pin "P$AC17") (pinfunction "P0.21_P$AC17") (pintype "bidirectional"))
    )
    (net (code "61") (name "P0.22") (class "Default")
      (node (ref "U1") (pin "P$AD18") (pinfunction "P0.22_P$AD18") (pintype "bidirectional"))
    )
    (net (code "62") (name "P0.23") (class "Default")
      (node (ref "U1") (pin "P$AC19") (pinfunction "P0.23_P$AC19") (pintype "bidirectional"))
    )
    (net (code "63") (name "P0.24") (class "Default")
      (node (ref "U1") (pin "P$AD20") (pinfunction "P0.24_P$AD20") (pintype "bidirectional"))
    )
    (net (code "64") (name "P0.25") (class "Default")
      (node (ref "U1") (pin "P$AC21") (pinfunction "P0.25_P$AC21") (pintype "bidirectional"))
    )
    (net (code "65") (name "P0.26") (class "Default")
      (node (ref "U1") (pin "P$G1") (pinfunction "P0.26_P$G1") (pintype "bidirectional"))
    )
    (net (code "66") (name "P0.27") (class "Default")
      (node (ref "U1") (pin "P$H2") (pinfunction "P0.27_P$H2") (pintype "bidirectional"))
    )
    (net (code "67") (name "P0.28") (class "Default")
      (node (ref "U1") (pin "P$B11") (pinfunction "P0.28/AIN4_P$B11") (pintype "bidirectional"))
    )
    (net (code "68") (name "P0.29") (class "Default")
      (node (ref "U1") (pin "P$A10") (pinfunction "P0.29/AIN5_P$A10") (pintype "bidirectional"))
    )
    (net (code "69") (name "P0.30") (class "Default")
      (node (ref "U1") (pin "P$B9") (pinfunction "P0.30/AIN6_P$B9") (pintype "bidirectional"))
    )
    (net (code "70") (name "P0.31") (class "Default")
      (node (ref "U1") (pin "P$A8") (pinfunction "P0.31/AIN7_P$A8") (pintype "bidirectional"))
    )
    (net (code "71") (name "P1.01") (class "Default")
      (node (ref "Q1") (pin "1") (pinfunction "G_1") (pintype "bidirectional"))
      (node (ref "R_PWR_EPD") (pin "1") (pinfunction "1_1") (pintype "bidirectional"))
      (node (ref "U1") (pin "P$Y23") (pinfunction "P1.01_P$Y23") (pintype "bidirectional"))
    )
    (net (code "72") (name "P1.02") (class "Default")
      (node (ref "C29") (pin "2") (pinfunction "2_2") (pintype "passive"))
      (node (ref "C30") (pin "2") (pinfunction "2_2") (pintype "passive"))
      (node (ref "C31") (pin "2") (pinfunction "2_2") (pintype "passive"))
      (node (ref "R5") (pin "1") (pinfunction "1_1") (pintype "bidirectional"))
      (node (ref "R7") (pin "1") (pinfunction "1_1") (pintype "bidirectional"))
      (node (ref "R8") (pin "1") (pinfunction "1_1") (pintype "bidirectional"))
      (node (ref "SW_DN") (pin "2") (pinfunction "2_2") (pintype "passive"))
      (node (ref "SW_ENT") (pin "2") (pinfunction "2_2") (pintype "passive"))
      (node (ref "SW_UP") (pin "2") (pinfunction "2_2") (pintype "passive"))
      (node (ref "U1") (pin "P$W24") (pinfunction "P1.02_P$W24") (pintype "bidirectional"))
    )
    (net (code "73") (name "P1.03") (class "Default")
      (node (ref "U1") (pin "P$V23") (pinfunction "P1.03_P$V23") (pintype "bidirectional"))
    )
    (net (code "74") (name "P1.04") (class "Default")
      (node (ref "U1") (pin "P$U24") (pinfunction "P1.04_P$U24") (pintype "bidirectional"))
    )
    (net (code "75") (name "P1.05") (class "Default")
      (node (ref "U1") (pin "P$T23") (pinfunction "P1.05_P$T23") (pintype "bidirectional"))
    )
    (net (code "76") (name "P1.06") (class "Default")
      (node (ref "U1") (pin "P$R24") (pinfunction "P1.06_P$R24") (pintype "bidirectional"))
    )
    (net (code "77") (name "P1.07") (class "Default")
      (node (ref "U1") (pin "P$P23") (pinfunction "P1.07_P$P23") (pintype "bidirectional"))
    )
    (net (code "78") (name "P1.09") (class "Default")
      (node (ref "U1") (pin "P$R1") (pinfunction "P1.09_P$R1") (pintype "bidirectional"))
    )
    (net (code "79") (name "P1.10") (class "Default")
      (node (ref "U1") (pin "P$A20") (pinfunction "P1.10_P$A20") (pintype "bidirectional"))
    )
    (net (code "80") (name "P1.11") (class "Default")
      (node (ref "U1") (pin "P$B19") (pinfunction "P1.11_P$B19") (pintype "bidirectional"))
    )
    (net (code "81") (name "P1.12") (class "Default")
      (node (ref "U1") (pin "P$B17") (pinfunction "P1.12_P$B17") (pintype "bidirectional"))
    )
    (net (code "82") (name "P1.13") (class "Default")
      (node (ref "U1") (pin "P$A16") (pinfunction "P1.13_P$A16") (pintype "bidirectional"))
    )
    (net (code "83") (name "P1.14") (class "Default")
      (node (ref "U1") (pin "P$B15") (pinfunction "P1.14_P$B15") (pintype "bidirectional"))
    )
    (net (code "84") (name "P1.15") (class "Default")
      (node (ref "U1") (pin "P$A14") (pinfunction "P1.15_P$A14") (pintype "bidirectional"))
    )
    (net (code "85") (name "PMIC_INT") (class "Default")
      (node (ref "IC1") (pin "A1") (pinfunction "~{INT}_A1") (pintype "bidirectional"))
      (node (ref "U1") (pin "P$T2") (pinfunction "P0.11_P$T2") (pintype "bidirectional"))
    )
    (net (code "86") (name "PREVGH") (class "Default")
      (node (ref "D5") (pin "1") (pinfunction "K_1") (pintype "bidirectional"))
      (node (ref "EPD_C9") (pin "2") (pinfunction "2_2") (pintype "passive"))
      (node (ref "J1") (pin "21") (pinfunction "21_21") (pintype "bidirectional"))
    )
    (net (code "87") (name "PREVGL") (class "Default")
      (node (ref "D2") (pin "2") (pinfunction "A_2") (pintype "bidirectional"))
      (node (ref "EPD_C11") (pin "2") (pinfunction "2_2") (pintype "passive"))
      (node (ref "J1") (pin "23") (pinfunction "23_23") (pintype "bidirectional"))
    )
    (net (code "88") (name "RESE") (class "Default")
      (node (ref "J1") (pin "3") (pinfunction "3_3") (pintype "bidirectional"))
      (node (ref "Q3") (pin "2") (pinfunction "S_2") (pintype "bidirectional"))
      (node (ref "R1_EP_DR") (pin "2") (pinfunction "2_2") (pintype "bidirectional"))
    )
    (net (code "89") (name "RESET") (class "Default")
      (node (ref "J2") (pin "6") (pinfunction "6_6") (pintype "bidirectional"))
      (node (ref "TP_RESET") (pin "TP") (pinfunction "TP_TP") (pintype "input"))
      (node (ref "U1") (pin "P$AC13") (pinfunction "P0.18/RESET_P$AC13") (pintype "bidirectional"))
    )
    (net (code "90") (name "SCK") (class "Default")
      (node (ref "J1") (pin "13") (pinfunction "13_13") (pintype "bidirectional"))
      (node (ref "U1") (pin "P$A12") (pinfunction "P0.02/AIN0_P$A12") (pintype "bidirectional"))
    )
    (net (code "91") (name "SCL") (class "Default")
      (node (ref "IC1") (pin "B1") (pinfunction "SCL_B1") (pintype "bidirectional"))
      (node (ref "IC2") (pin "C1") (pinfunction "SCL_C1") (pintype "bidirectional"))
      (node (ref "IC3") (pin "12") (pinfunction "SCX_12") (pintype "bidirectional"))
      (node (ref "R17") (pin "2") (pinfunction "2_2") (pintype "bidirectional"))
      (node (ref "R4") (pin "1") (pinfunction "1_1") (pintype "bidirectional"))
      (node (ref "TP_SCL") (pin "TP") (pinfunction "TP_TP") (pintype "input"))
      (node (ref "U1") (pin "P$M2") (pinfunction "P0.07_P$M2") (pintype "bidirectional"))
      (node (ref "U3") (pin "7") (pinfunction "SCL_7") (pintype "input"))
    )
    (net (code "92") (name "SDA") (class "Default")
      (node (ref "IC1") (pin "C1") (pinfunction "SDA_C1") (pintype "bidirectional"))
      (node (ref "IC2") (pin "B2") (pinfunction "SDA_B2") (pintype "bidirectional"))
      (node (ref "IC3") (pin "2") (pinfunction "SDX_2") (pintype "bidirectional"))
      (node (ref "R18") (pin "2") (pinfunction "2_2") (pintype "bidirectional"))
      (node (ref "R2") (pin "1") (pinfunction "1_1") (pintype "bidirectional"))
      (node (ref "TP_SDA") (pin "TP") (pinfunction "TP_TP") (pintype "input"))
      (node (ref "U1") (pin "P$L1") (pinfunction "P0.06_P$L1") (pintype "bidirectional"))
      (node (ref "U3") (pin "8") (pinfunction "SDA_8") (pintype "bidirectional"))
    )
    (net (code "93") (name "SWDCLK") (class "Default")
      (node (ref "J2") (pin "4") (pinfunction "4_4") (pintype "bidirectional"))
      (node (ref "TP_SWDCLK") (pin "TP") (pinfunction "TP_TP") (pintype "input"))
      (node (ref "U1") (pin "P$AA24") (pinfunction "SWDCLK_P$AA24") (pintype "input"))
    )
    (net (code "94") (name "SWDIO") (class "Default")
      (node (ref "J2") (pin "2") (pinfunction "2_2") (pintype "bidirectional"))
      (node (ref "TP_SWDIO") (pin "TP") (pinfunction "TP_TP") (pintype "input"))
      (node (ref "U1") (pin "P$AC24") (pinfunction "SWDIO_P$AC24") (pintype "bidirectional"))
    )
    (net (code "95") (name "SWO") (class "Default")
      (node (ref "TP_SWO") (pin "TP") (pinfunction "TP_TP") (pintype "input"))
      (node (ref "U1") (pin "P$AD22") (pinfunction "P1.00_P$AD22") (pintype "bidirectional"))
    )
    (net (code "96") (name "VBAT") (class "Default")
      (node (ref "C27") (pin "2") (pinfunction "2_2") (pintype "passive"))
      (node (ref "C37") (pin "2") (pinfunction "2_2") (pintype "passive"))
      (node (ref "IC1") (pin "C2") (pinfunction "BAT_C2") (pintype "bidirectional"))
      (node (ref "TP_VBAT") (pin "TP") (pinfunction "TP_TP") (pintype "input"))
      (node (ref "U3") (pin "2") (pinfunction "CELL_2") (pintype "power_in"))
      (node (ref "U3") (pin "3") (pinfunction "VDD_3") (pintype "power_in"))
    )
    (net (code "97") (name "VBUS") (class "Default")
      (node (ref "C21") (pin "1") (pinfunction "1_1") (pintype "passive"))
      (node (ref "C38") (pin "2") (pinfunction "2_2") (pintype "passive"))
      (node (ref "C42") (pin "1") (pinfunction "1_1") (pintype "passive"))
      (node (ref "C43") (pin "1") (pinfunction "1_1") (pintype "passive"))
      (node (ref "D3") (pin "5") (pinfunction "VBUS_5") (pintype "bidirectional"))
      (node (ref "IC1") (pin "A2") (pinfunction "IN_A2") (pintype "bidirectional"))
      (node (ref "J4") (pin "A4_B9") (pinfunction "VBUS_A4_B9") (pintype "power_in"))
      (node (ref "J4") (pin "A9_B4") (pinfunction "VBUS_A9_B4") (pintype "power_in"))
      (node (ref "U1") (pin "P$AD2") (pinfunction "VBUS_P$AD2") (pintype "power_in"))
    )
    (net (code "98") (name "VREG") (class "Default")
      (node (ref "C23") (pin "2") (pinfunction "2_2") (pintype "passive"))
      (node (ref "C24") (pin "2") (pinfunction "2_2") (pintype "passive"))
      (node (ref "C39") (pin "1") (pinfunction "1_1") (pintype "passive"))
      (node (ref "IC1") (pin "B2") (pinfunction "SYS_B2") (pintype "bidirectional"))
      (node (ref "IC9") (pin "A1") (pinfunction "EN_A1") (pintype "bidirectional"))
      (node (ref "IC9") (pin "A2") (pinfunction "VIN_1_A2") (pintype "bidirectional"))
      (node (ref "IC9") (pin "A3") (pinfunction "VIN_2_A3") (pintype "bidirectional"))
      (node (ref "TP_VREG") (pin "TP") (pinfunction "TP_TP") (pintype "input"))
    )
    (net (code "99") (name "unconnected-(ANT1-NC-Pad2)") (class "Default")
      (node (ref "ANT1") (pin "2") (pinfunction "NC_2") (pintype "no_connect"))
    )
    (net (code "100") (name "unconnected-(IC3-ASCL-Pad11)") (class "Default")
      (node (ref "IC3") (pin "11") (pinfunction "ASCL_11") (pintype "bidirectional"))
    )
    (net (code "101") (name "unconnected-(IC3-ASDA-Pad4)") (class "Default")
      (node (ref "IC3") (pin "4") (pinfunction "ASDA_4") (pintype "bidirectional"))
    )
    (net (code "102") (name "unconnected-(J1-Pad1)") (class "Default")
      (node (ref "J1") (pin "1") (pinfunction "1_1") (pintype "bidirectional"))
    )
    (net (code "103") (name "unconnected-(J1-Pad6)") (class "Default")
      (node (ref "J1") (pin "6") (pinfunction "6_6") (pintype "bidirectional"))
    )
    (net (code "104") (name "unconnected-(J1-Pad7)") (class "Default")
      (node (ref "J1") (pin "7") (pinfunction "7_7") (pintype "bidirectional"))
    )
    (net (code "105") (name "unconnected-(J4-SBU1-PadA8)") (class "Default")
      (node (ref "J4") (pin "A8") (pinfunction "SBU1_A8") (pintype "bidirectional"))
    )
    (net (code "106") (name "unconnected-(J4-SBU2-PadB8)") (class "Default")
      (node (ref "J4") (pin "B8") (pinfunction "SBU2_B8") (pintype "bidirectional"))
    )
    (net (code "107") (name "unconnected-(U1-DCCH-PadP$AB2)") (class "Default")
      (node (ref "U1") (pin "P$AB2") (pinfunction "DCCH_P$AB2") (pintype "bidirectional"))
    )
  )
)
